# Miscellaneous.net
KiCad netlist of a schematic drawn in Altium Designer
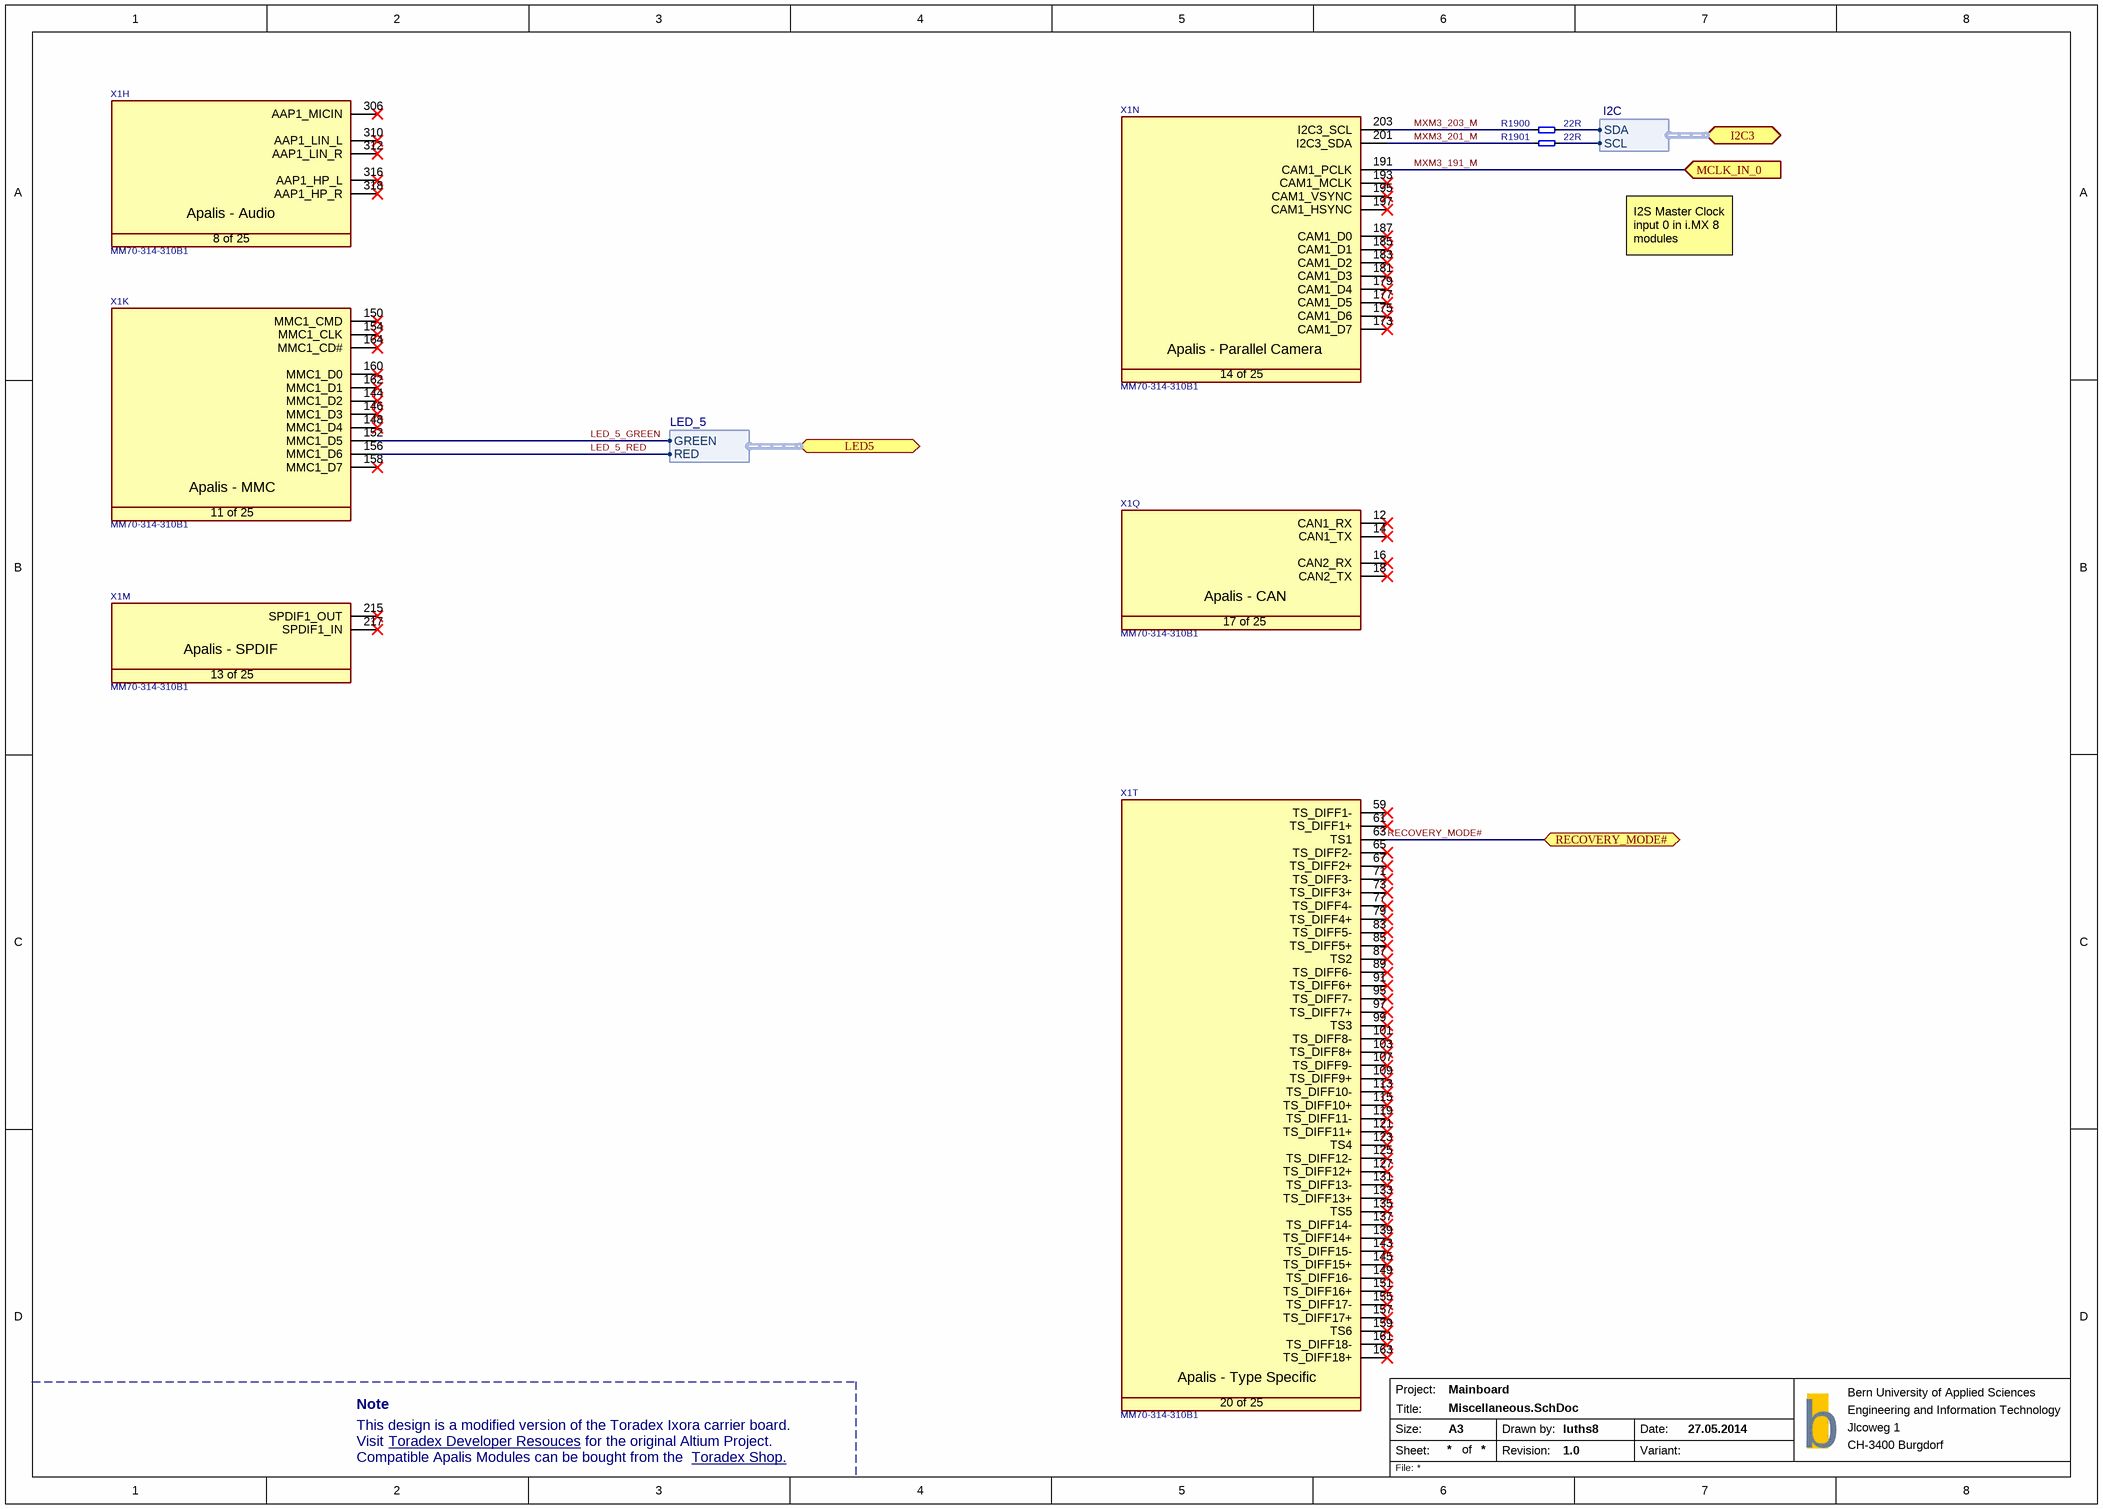
[diagram p0: Miscellaneous.SchDoc]

(export (version "E")
  (design (tool "Eeschema 10.0.6"))
  (components
    (comp (ref "R1900")
      (value "22R")
      (footprint "SMD0603RES")
      (description "Resistor 22 ohm 63mW 5% 0603")
      (fields (field (name "TOLERANCE") "5%"))
      (libsource (lib "Ixora") (part "R-22R-63mW-5%-0402"))
    )
    (comp (ref "R1901")
      (value "22R")
      (footprint "SMD0603RES")
      (description "Resistor 22 ohm 63mW 5% 0603")
      (fields (field (name "TOLERANCE") "5%"))
      (libsource (lib "Ixora") (part "R-22R-63mW-5%-0402"))
    )
    (comp (ref "X1")
      (value "CON-JAE-MM70-314-310B1-314-0.5mm")
      (footprint "T_JAE_MM70-314-310B1")
      (description "MXM3 Connector")
      (fields (field (name "MANUFACTURER PART NO.") "MM70-314-310B1"))
      (libsource (lib "Ixora") (part "CON-JAE-MM70-314-310B1-314-0.5mm"))
    )
  )
  (nets
    (net (code "3") (name "/LED_5_GREEN") (class "Default")
      (node (ref "X1") (pin "152") (pinfunction "MMC1_D5_152") (pintype "passive"))
    )
    (net (code "4") (name "/LED_5_RED") (class "Default")
      (node (ref "X1") (pin "156") (pinfunction "MMC1_D6_156") (pintype "passive"))
    )
    (net (code "5") (name "/MXM3_191_M") (class "Default")
      (node (ref "X1") (pin "191") (pinfunction "CAM1_PCLK_191") (pintype "passive"))
    )
    (net (code "6") (name "/MXM3_201_M") (class "Default")
      (node (ref "R1901") (pin "1") (pinfunction "1_1") (pintype "passive"))
      (node (ref "X1") (pin "201") (pinfunction "I2C3_SDA_201") (pintype "passive"))
    )
    (net (code "7") (name "/MXM3_203_M") (class "Default")
      (node (ref "R1900") (pin "1") (pinfunction "1_1") (pintype "passive"))
      (node (ref "X1") (pin "203") (pinfunction "I2C3_SCL_203") (pintype "passive"))
    )
    (net (code "8") (name "/RECOVERY_MODE#") (class "Default")
      (node (ref "X1") (pin "63") (pinfunction "TS1_63") (pintype "passive"))
    )
    (net (code "9") (name "/SCL") (class "Default")
      (node (ref "R1901") (pin "2") (pinfunction "2_2") (pintype "passive"))
    )
    (net (code "10") (name "/SDA") (class "Default")
      (node (ref "R1900") (pin "2") (pinfunction "2_2") (pintype "passive"))
    )
    (net (code "13") (name "unconnected-(X1H-AAP1_HP_L-Pad316)") (class "Default")
      (node (ref "X1") (pin "316") (pinfunction "AAP1_HP_L_316") (pintype "passive+no_connect"))
    )
    (net (code "14") (name "unconnected-(X1H-AAP1_HP_R-Pad318)") (class "Default")
      (node (ref "X1") (pin "318") (pinfunction "AAP1_HP_R_318") (pintype "passive+no_connect"))
    )
    (net (code "15") (name "unconnected-(X1H-AAP1_LIN_L-Pad310)") (class "Default")
      (node (ref "X1") (pin "310") (pinfunction "AAP1_LIN_L_310") (pintype "passive+no_connect"))
    )
    (net (code "16") (name "unconnected-(X1H-AAP1_LIN_R-Pad312)") (class "Default")
      (node (ref "X1") (pin "312") (pinfunction "AAP1_LIN_R_312") (pintype "passive+no_connect"))
    )
    (net (code "17") (name "unconnected-(X1H-AAP1_MICIN-Pad306)") (class "Default")
      (node (ref "X1") (pin "306") (pinfunction "AAP1_MICIN_306") (pintype "passive+no_connect"))
    )
    (net (code "18") (name "unconnected-(X1K-MMC1_CD#-Pad164)") (class "Default")
      (node (ref "X1") (pin "164") (pinfunction "MMC1_CD#_164") (pintype "passive+no_connect"))
    )
    (net (code "19") (name "unconnected-(X1K-MMC1_CLK-Pad154)") (class "Default")
      (node (ref "X1") (pin "154") (pinfunction "MMC1_CLK_154") (pintype "passive+no_connect"))
    )
    (net (code "20") (name "unconnected-(X1K-MMC1_CMD-Pad150)") (class "Default")
      (node (ref "X1") (pin "150") (pinfunction "MMC1_CMD_150") (pintype "passive+no_connect"))
    )
    (net (code "21") (name "unconnected-(X1K-MMC1_D0-Pad160)") (class "Default")
      (node (ref "X1") (pin "160") (pinfunction "MMC1_D0_160") (pintype "passive+no_connect"))
    )
    (net (code "22") (name "unconnected-(X1K-MMC1_D1-Pad162)") (class "Default")
      (node (ref "X1") (pin "162") (pinfunction "MMC1_D1_162") (pintype "passive+no_connect"))
    )
    (net (code "23") (name "unconnected-(X1K-MMC1_D2-Pad144)") (class "Default")
      (node (ref "X1") (pin "144") (pinfunction "MMC1_D2_144") (pintype "passive+no_connect"))
    )
    (net (code "24") (name "unconnected-(X1K-MMC1_D3-Pad146)") (class "Default")
      (node (ref "X1") (pin "146") (pinfunction "MMC1_D3_146") (pintype "passive+no_connect"))
    )
    (net (code "25") (name "unconnected-(X1K-MMC1_D4-Pad148)") (class "Default")
      (node (ref "X1") (pin "148") (pinfunction "MMC1_D4_148") (pintype "passive+no_connect"))
    )
    (net (code "26") (name "unconnected-(X1K-MMC1_D7-Pad158)") (class "Default")
      (node (ref "X1") (pin "158") (pinfunction "MMC1_D7_158") (pintype "passive+no_connect"))
    )
    (net (code "27") (name "unconnected-(X1M-SPDIF1_IN-Pad217)") (class "Default")
      (node (ref "X1") (pin "217") (pinfunction "SPDIF1_IN_217") (pintype "passive+no_connect"))
    )
    (net (code "28") (name "unconnected-(X1M-SPDIF1_OUT-Pad215)") (class "Default")
      (node (ref "X1") (pin "215") (pinfunction "SPDIF1_OUT_215") (pintype "passive+no_connect"))
    )
    (net (code "29") (name "unconnected-(X1N-CAM1_D0-Pad187)") (class "Default")
      (node (ref "X1") (pin "187") (pinfunction "CAM1_D0_187") (pintype "passive+no_connect"))
    )
    (net (code "30") (name "unconnected-(X1N-CAM1_D1-Pad185)") (class "Default")
      (node (ref "X1") (pin "185") (pinfunction "CAM1_D1_185") (pintype "passive+no_connect"))
    )
    (net (code "31") (name "unconnected-(X1N-CAM1_D2-Pad183)") (class "Default")
      (node (ref "X1") (pin "183") (pinfunction "CAM1_D2_183") (pintype "passive+no_connect"))
    )
    (net (code "32") (name "unconnected-(X1N-CAM1_D3-Pad181)") (class "Default")
      (node (ref "X1") (pin "181") (pinfunction "CAM1_D3_181") (pintype "passive+no_connect"))
    )
    (net (code "33") (name "unconnected-(X1N-CAM1_D4-Pad179)") (class "Default")
      (node (ref "X1") (pin "179") (pinfunction "CAM1_D4_179") (pintype "passive+no_connect"))
    )
    (net (code "34") (name "unconnected-(X1N-CAM1_D5-Pad177)") (class "Default")
      (node (ref "X1") (pin "177") (pinfunction "CAM1_D5_177") (pintype "passive+no_connect"))
    )
    (net (code "35") (name "unconnected-(X1N-CAM1_D6-Pad175)") (class "Default")
      (node (ref "X1") (pin "175") (pinfunction "CAM1_D6_175") (pintype "passive+no_connect"))
    )
    (net (code "36") (name "unconnected-(X1N-CAM1_D7-Pad173)") (class "Default")
      (node (ref "X1") (pin "173") (pinfunction "CAM1_D7_173") (pintype "passive+no_connect"))
    )
    (net (code "37") (name "unconnected-(X1N-CAM1_HSYNC-Pad197)") (class "Default")
      (node (ref "X1") (pin "197") (pinfunction "CAM1_HSYNC_197") (pintype "passive+no_connect"))
    )
    (net (code "38") (name "unconnected-(X1N-CAM1_MCLK-Pad193)") (class "Default")
      (node (ref "X1") (pin "193") (pinfunction "CAM1_MCLK_193") (pintype "passive+no_connect"))
    )
    (net (code "39") (name "unconnected-(X1N-CAM1_VSYNC-Pad195)") (class "Default")
      (node (ref "X1") (pin "195") (pinfunction "CAM1_VSYNC_195") (pintype "passive+no_connect"))
    )
    (net (code "40") (name "unconnected-(X1Q-CAN1_RX-Pad12)") (class "Default")
      (node (ref "X1") (pin "12") (pinfunction "CAN1_RX_12") (pintype "passive+no_connect"))
    )
    (net (code "41") (name "unconnected-(X1Q-CAN1_TX-Pad14)") (class "Default")
      (node (ref "X1") (pin "14") (pinfunction "CAN1_TX_14") (pintype "passive+no_connect"))
    )
    (net (code "42") (name "unconnected-(X1Q-CAN2_RX-Pad16)") (class "Default")
      (node (ref "X1") (pin "16") (pinfunction "CAN2_RX_16") (pintype "passive+no_connect"))
    )
    (net (code "43") (name "unconnected-(X1Q-CAN2_TX-Pad18)") (class "Default")
      (node (ref "X1") (pin "18") (pinfunction "CAN2_TX_18") (pintype "passive+no_connect"))
    )
    (net (code "44") (name "unconnected-(X1T-TS2-Pad87)") (class "Default")
      (node (ref "X1") (pin "87") (pinfunction "TS2_87") (pintype "passive+no_connect"))
    )
    (net (code "45") (name "unconnected-(X1T-TS3-Pad99)") (class "Default")
      (node (ref "X1") (pin "99") (pinfunction "TS3_99") (pintype "passive+no_connect"))
    )
    (net (code "46") (name "unconnected-(X1T-TS4-Pad123)") (class "Default")
      (node (ref "X1") (pin "123") (pinfunction "TS4_123") (pintype "passive+no_connect"))
    )
    (net (code "47") (name "unconnected-(X1T-TS5-Pad135)") (class "Default")
      (node (ref "X1") (pin "135") (pinfunction "TS5_135") (pintype "passive+no_connect"))
    )
    (net (code "48") (name "unconnected-(X1T-TS6-Pad159)") (class "Default")
      (node (ref "X1") (pin "159") (pinfunction "TS6_159") (pintype "passive+no_connect"))
    )
    (net (code "49") (name "unconnected-(X1T-TS_DIFF1+-Pad61)") (class "Default")
      (node (ref "X1") (pin "61") (pinfunction "TS_DIFF1+_61") (pintype "passive+no_connect"))
    )
    (net (code "50") (name "unconnected-(X1T-TS_DIFF1--Pad59)") (class "Default")
      (node (ref "X1") (pin "59") (pinfunction "TS_DIFF1-_59") (pintype "passive+no_connect"))
    )
    (net (code "51") (name "unconnected-(X1T-TS_DIFF2+-Pad67)") (class "Default")
      (node (ref "X1") (pin "67") (pinfunction "TS_DIFF2+_67") (pintype "passive+no_connect"))
    )
    (net (code "52") (name "unconnected-(X1T-TS_DIFF2--Pad65)") (class "Default")
      (node (ref "X1") (pin "65") (pinfunction "TS_DIFF2-_65") (pintype "passive+no_connect"))
    )
    (net (code "53") (name "unconnected-(X1T-TS_DIFF3+-Pad73)") (class "Default")
      (node (ref "X1") (pin "73") (pinfunction "TS_DIFF3+_73") (pintype "passive+no_connect"))
    )
    (net (code "54") (name "unconnected-(X1T-TS_DIFF3--Pad71)") (class "Default")
      (node (ref "X1") (pin "71") (pinfunction "TS_DIFF3-_71") (pintype "passive+no_connect"))
    )
    (net (code "55") (name "unconnected-(X1T-TS_DIFF4+-Pad79)") (class "Default")
      (node (ref "X1") (pin "79") (pinfunction "TS_DIFF4+_79") (pintype "passive+no_connect"))
    )
    (net (code "56") (name "unconnected-(X1T-TS_DIFF4--Pad77)") (class "Default")
      (node (ref "X1") (pin "77") (pinfunction "TS_DIFF4-_77") (pintype "passive+no_connect"))
    )
    (net (code "57") (name "unconnected-(X1T-TS_DIFF5+-Pad85)") (class "Default")
      (node (ref "X1") (pin "85") (pinfunction "TS_DIFF5+_85") (pintype "passive+no_connect"))
    )
    (net (code "58") (name "unconnected-(X1T-TS_DIFF5--Pad83)") (class "Default")
      (node (ref "X1") (pin "83") (pinfunction "TS_DIFF5-_83") (pintype "passive+no_connect"))
    )
    (net (code "59") (name "unconnected-(X1T-TS_DIFF6+-Pad91)") (class "Default")
      (node (ref "X1") (pin "91") (pinfunction "TS_DIFF6+_91") (pintype "passive+no_connect"))
    )
    (net (code "60") (name "unconnected-(X1T-TS_DIFF6--Pad89)") (class "Default")
      (node (ref "X1") (pin "89") (pinfunction "TS_DIFF6-_89") (pintype "passive+no_connect"))
    )
    (net (code "61") (name "unconnected-(X1T-TS_DIFF7+-Pad97)") (class "Default")
      (node (ref "X1") (pin "97") (pinfunction "TS_DIFF7+_97") (pintype "passive+no_connect"))
    )
    (net (code "62") (name "unconnected-(X1T-TS_DIFF7--Pad95)") (class "Default")
      (node (ref "X1") (pin "95") (pinfunction "TS_DIFF7-_95") (pintype "passive+no_connect"))
    )
    (net (code "63") (name "unconnected-(X1T-TS_DIFF8+-Pad103)") (class "Default")
      (node (ref "X1") (pin "103") (pinfunction "TS_DIFF8+_103") (pintype "passive+no_connect"))
    )
    (net (code "64") (name "unconnected-(X1T-TS_DIFF8--Pad101)") (class "Default")
      (node (ref "X1") (pin "101") (pinfunction "TS_DIFF8-_101") (pintype "passive+no_connect"))
    )
    (net (code "65") (name "unconnected-(X1T-TS_DIFF9+-Pad109)") (class "Default")
      (node (ref "X1") (pin "109") (pinfunction "TS_DIFF9+_109") (pintype "passive+no_connect"))
    )
    (net (code "66") (name "unconnected-(X1T-TS_DIFF9--Pad107)") (class "Default")
      (node (ref "X1") (pin "107") (pinfunction "TS_DIFF9-_107") (pintype "passive+no_connect"))
    )
    (net (code "67") (name "unconnected-(X1T-TS_DIFF10+-Pad115)") (class "Default")
      (node (ref "X1") (pin "115") (pinfunction "TS_DIFF10+_115") (pintype "passive+no_connect"))
    )
    (net (code "68") (name "unconnected-(X1T-TS_DIFF10--Pad113)") (class "Default")
      (node (ref "X1") (pin "113") (pinfunction "TS_DIFF10-_113") (pintype "passive+no_connect"))
    )
    (net (code "69") (name "unconnected-(X1T-TS_DIFF11+-Pad121)") (class "Default")
      (node (ref "X1") (pin "121") (pinfunction "TS_DIFF11+_121") (pintype "passive+no_connect"))
    )
    (net (code "70") (name "unconnected-(X1T-TS_DIFF11--Pad119)") (class "Default")
      (node (ref "X1") (pin "119") (pinfunction "TS_DIFF11-_119") (pintype "passive+no_connect"))
    )
    (net (code "71") (name "unconnected-(X1T-TS_DIFF12+-Pad127)") (class "Default")
      (node (ref "X1") (pin "127") (pinfunction "TS_DIFF12+_127") (pintype "passive+no_connect"))
    )
    (net (code "72") (name "unconnected-(X1T-TS_DIFF12--Pad125)") (class "Default")
      (node (ref "X1") (pin "125") (pinfunction "TS_DIFF12-_125") (pintype "passive+no_connect"))
    )
    (net (code "73") (name "unconnected-(X1T-TS_DIFF13+-Pad133)") (class "Default")
      (node (ref "X1") (pin "133") (pinfunction "TS_DIFF13+_133") (pintype "passive+no_connect"))
    )
    (net (code "74") (name "unconnected-(X1T-TS_DIFF13--Pad131)") (class "Default")
      (node (ref "X1") (pin "131") (pinfunction "TS_DIFF13-_131") (pintype "passive+no_connect"))
    )
    (net (code "75") (name "unconnected-(X1T-TS_DIFF14+-Pad139)") (class "Default")
      (node (ref "X1") (pin "139") (pinfunction "TS_DIFF14+_139") (pintype "passive+no_connect"))
    )
    (net (code "76") (name "unconnected-(X1T-TS_DIFF14--Pad137)") (class "Default")
      (node (ref "X1") (pin "137") (pinfunction "TS_DIFF14-_137") (pintype "passive+no_connect"))
    )
    (net (code "77") (name "unconnected-(X1T-TS_DIFF15+-Pad145)") (class "Default")
      (node (ref "X1") (pin "145") (pinfunction "TS_DIFF15+_145") (pintype "passive+no_connect"))
    )
    (net (code "78") (name "unconnected-(X1T-TS_DIFF15--Pad143)") (class "Default")
      (node (ref "X1") (pin "143") (pinfunction "TS_DIFF15-_143") (pintype "passive+no_connect"))
    )
    (net (code "79") (name "unconnected-(X1T-TS_DIFF16+-Pad151)") (class "Default")
      (node (ref "X1") (pin "151") (pinfunction "TS_DIFF16+_151") (pintype "passive+no_connect"))
    )
    (net (code "80") (name "unconnected-(X1T-TS_DIFF16--Pad149)") (class "Default")
      (node (ref "X1") (pin "149") (pinfunction "TS_DIFF16-_149") (pintype "passive+no_connect"))
    )
    (net (code "81") (name "unconnected-(X1T-TS_DIFF17+-Pad157)") (class "Default")
      (node (ref "X1") (pin "157") (pinfunction "TS_DIFF17+_157") (pintype "passive+no_connect"))
    )
    (net (code "82") (name "unconnected-(X1T-TS_DIFF17--Pad155)") (class "Default")
      (node (ref "X1") (pin "155") (pinfunction "TS_DIFF17-_155") (pintype "passive+no_connect"))
    )
    (net (code "83") (name "unconnected-(X1T-TS_DIFF18+-Pad163)") (class "Default")
      (node (ref "X1") (pin "163") (pinfunction "TS_DIFF18+_163") (pintype "passive+no_connect"))
    )
    (net (code "84") (name "unconnected-(X1T-TS_DIFF18--Pad161)") (class "Default")
      (node (ref "X1") (pin "161") (pinfunction "TS_DIFF18-_161") (pintype "passive+no_connect"))
    )
  )
)
